# HV1.net
KiCad netlist of a schematic drawn in Altium Designer
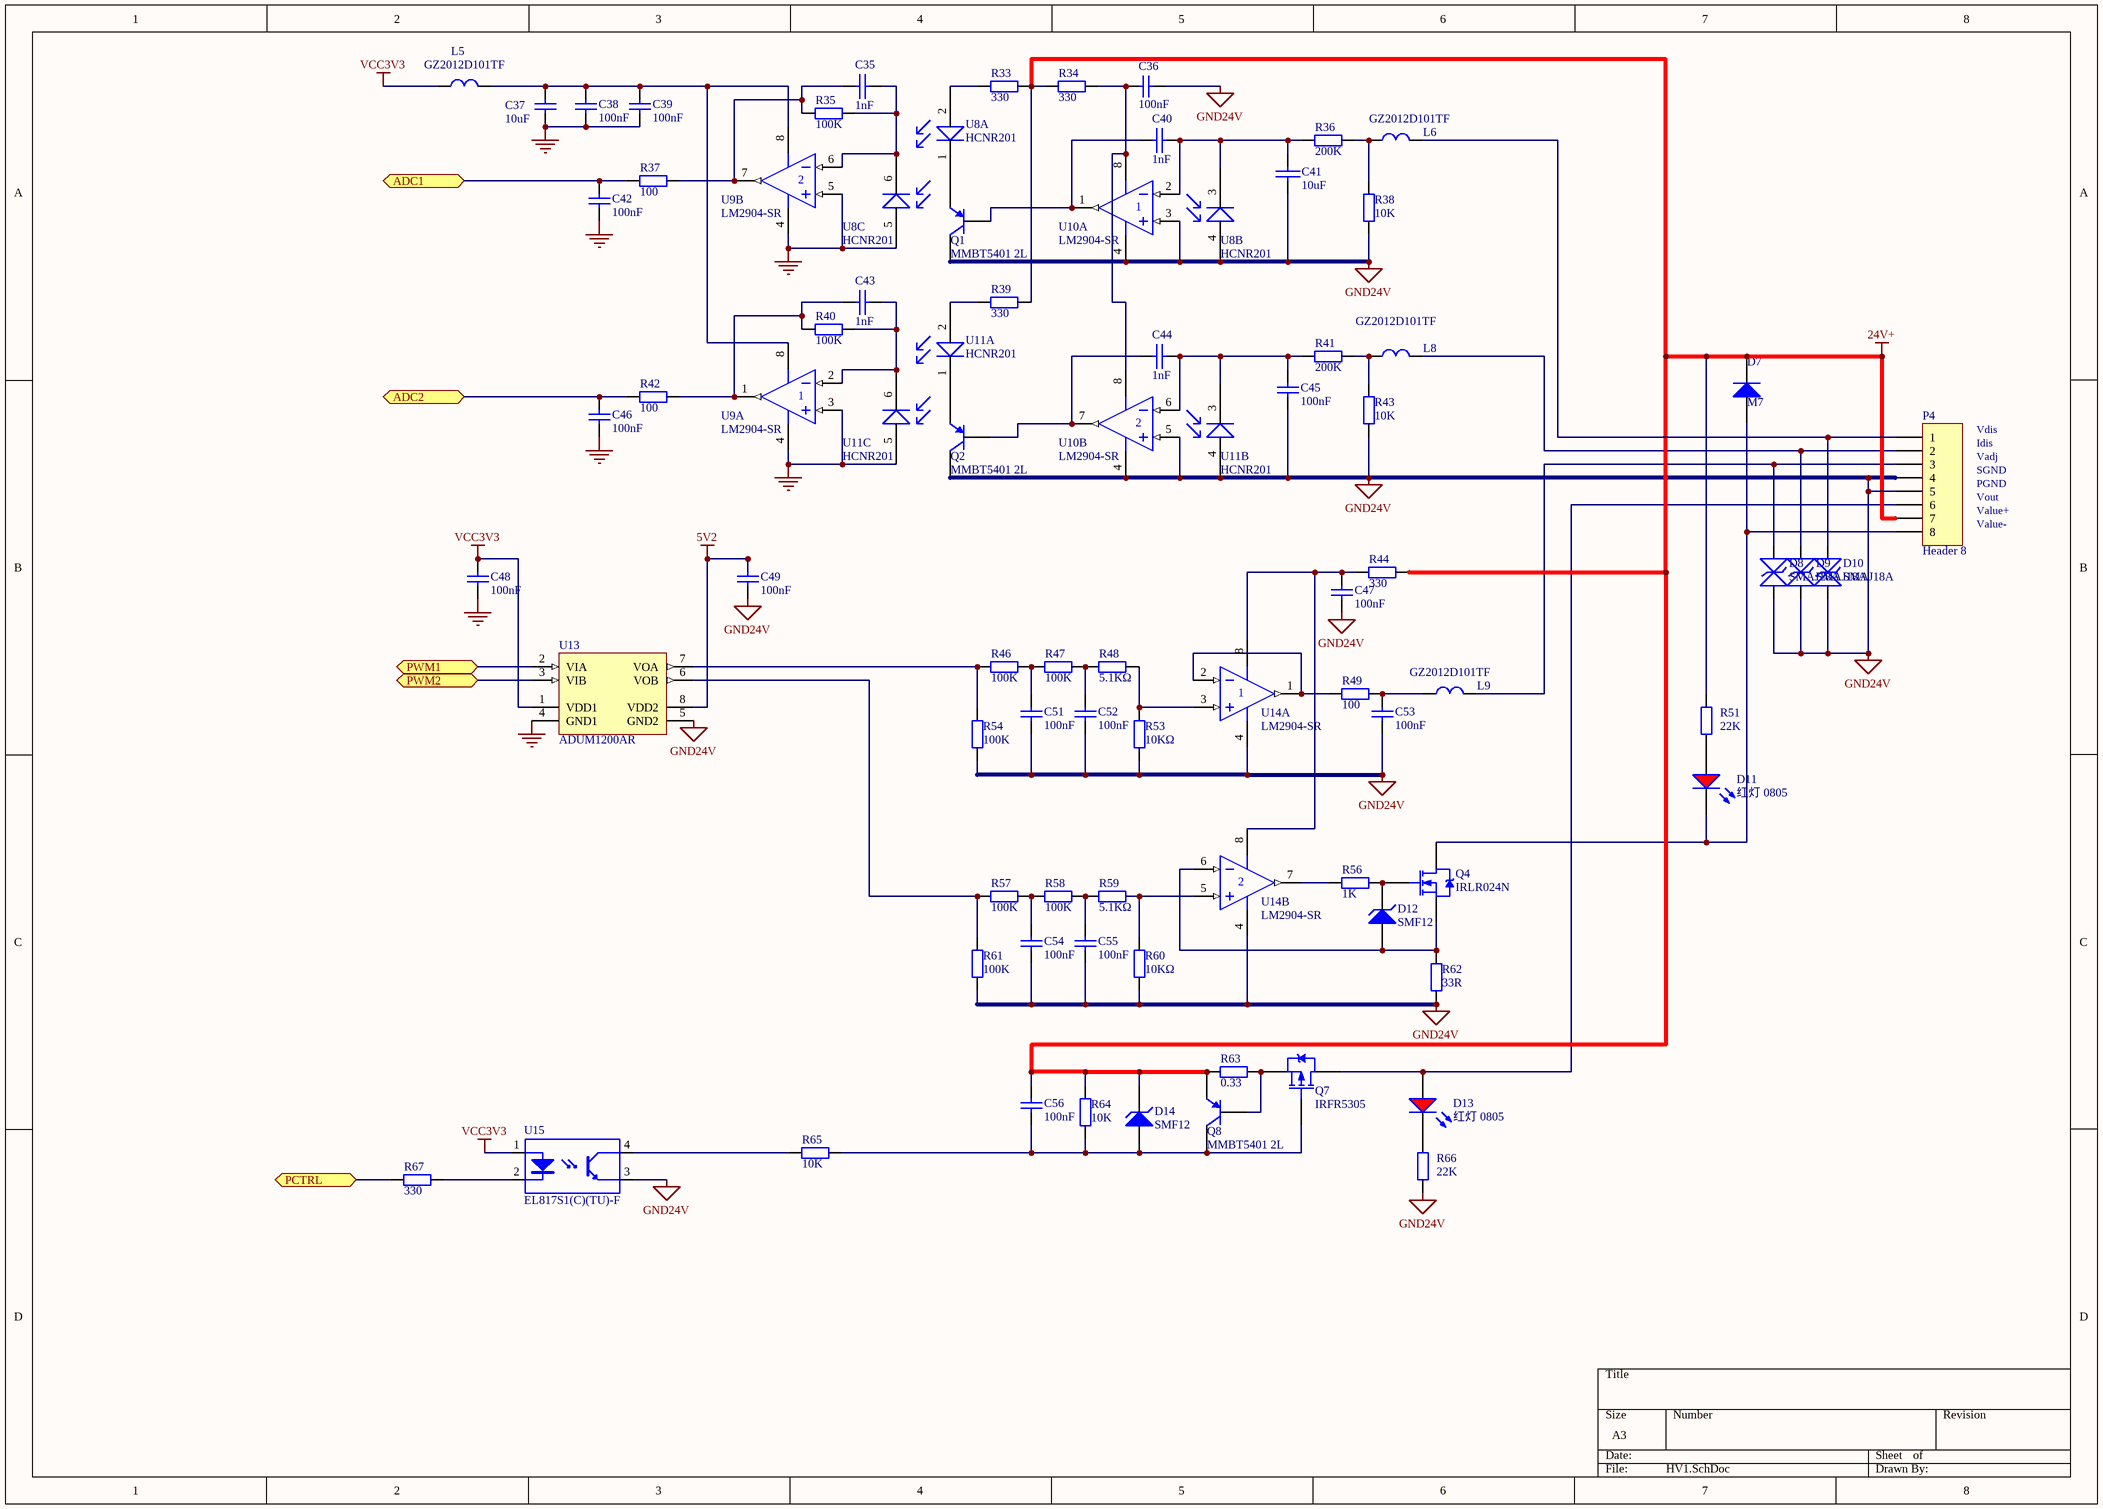
[diagram p0: HV1.SchDoc]

(export (version "E")
  (design (tool "Eeschema 10.0.6"))
  (components
    (comp (ref "C35")
      (value "1nF")
      (footprint "0805_C")
      (description "Capacitor")
      (libsource (lib "*") (part "CAP"))
    )
    (comp (ref "C36")
      (value "100nF")
      (footprint "0805_C")
      (description "贴片电容")
      (libsource (lib "Miscellaneous Devices LC") (part "0805 100nF(104) 10% 50V"))
    )
    (comp (ref "C37")
      (value "10uF")
      (footprint "0805_C")
      (description "贴片电容")
      (libsource (lib "Miscellaneous Devices LC") (part "1206 10uF (106) 10% 50V"))
    )
    (comp (ref "C38")
      (value "100nF")
      (footprint "0805_C")
      (description "贴片电容")
      (libsource (lib "Miscellaneous Devices LC") (part "0805 100nF(104) 10% 50V"))
    )
    (comp (ref "C39")
      (value "100nF")
      (footprint "0805_C")
      (description "贴片电容")
      (libsource (lib "Miscellaneous Devices LC") (part "0805 100nF(104) 10% 50V"))
    )
    (comp (ref "C40")
      (value "1nF")
      (footprint "0805_C")
      (description "Capacitor")
      (libsource (lib "*") (part "CAP"))
    )
    (comp (ref "C41")
      (value "10uF")
      (footprint "0805_C")
      (description "Capacitor")
      (libsource (lib "*") (part "CC"))
    )
    (comp (ref "C42")
      (value "100nF")
      (footprint "0805_C")
      (description "贴片电容")
      (libsource (lib "Miscellaneous Devices LC") (part "0805 100nF(104) 10% 50V"))
    )
    (comp (ref "C43")
      (value "1nF")
      (footprint "0805_C")
      (description "Capacitor")
      (libsource (lib "*") (part "CAP"))
    )
    (comp (ref "C44")
      (value "1nF")
      (footprint "0805_C")
      (description "Capacitor")
      (libsource (lib "*") (part "CAP"))
    )
    (comp (ref "C45")
      (value "100nF")
      (footprint "0805_C")
      (description "贴片电容")
      (libsource (lib "Miscellaneous Devices LC") (part "0805 100nF(104) 10% 50V"))
    )
    (comp (ref "C46")
      (value "100nF")
      (footprint "0805_C")
      (description "贴片电容")
      (libsource (lib "Miscellaneous Devices LC") (part "0805 100nF(104) 10% 50V"))
    )
    (comp (ref "C47")
      (value "100nF")
      (footprint "0805_C")
      (description "贴片电容")
      (libsource (lib "Miscellaneous Devices LC") (part "0805 100nF(104) 10% 50V"))
    )
    (comp (ref "C48")
      (value "100nF")
      (footprint "0805_C")
      (description "贴片电容")
      (libsource (lib "Miscellaneous Devices LC") (part "0805 100nF(104) 10% 50V"))
    )
    (comp (ref "C49")
      (value "100nF")
      (footprint "0805_C")
      (description "贴片电容")
      (libsource (lib "Miscellaneous Devices LC") (part "0805 100nF(104) 10% 50V"))
    )
    (comp (ref "C51")
      (value "100nF")
      (footprint "0805_C")
      (description "贴片电容")
      (libsource (lib "Miscellaneous Devices LC") (part "0805 100nF(104) 10% 50V"))
    )
    (comp (ref "C52")
      (value "100nF")
      (footprint "0805_C")
      (description "贴片电容")
      (libsource (lib "Miscellaneous Devices LC") (part "0805 100nF(104) 10% 50V"))
    )
    (comp (ref "C53")
      (value "100nF")
      (footprint "0805_C")
      (description "贴片电容")
      (libsource (lib "Miscellaneous Devices LC") (part "0805 100nF(104) 10% 50V"))
    )
    (comp (ref "C54")
      (value "100nF")
      (footprint "0805_C")
      (description "贴片电容")
      (libsource (lib "Miscellaneous Devices LC") (part "0805 100nF(104) 10% 50V"))
    )
    (comp (ref "C55")
      (value "100nF")
      (footprint "0805_C")
      (description "贴片电容")
      (libsource (lib "Miscellaneous Devices LC") (part "0805 100nF(104) 10% 50V"))
    )
    (comp (ref "C56")
      (value "100nF")
      (footprint "0805_C")
      (description "贴片电容")
      (libsource (lib "Miscellaneous Devices LC") (part "0805 100nF(104) 10% 50V"))
    )
    (comp (ref "D7")
      (value "M7")
      (footprint "SMA(DO-214AC)_S1")
      (description "二极管")
      (libsource (lib "Miscellaneous Devices LC") (part "SMA(DO-214AC) M7"))
    )
    (comp (ref "D8") (value "SMAJ18A") (footprint "SMA") (libsource (lib "IC") (part "TVS")))
    (comp (ref "D9") (value "SMAJ18A") (footprint "SMA") (libsource (lib "IC") (part "TVS")))
    (comp (ref "D10") (value "SMAJ18A") (footprint "SMA") (libsource (lib "IC") (part "TVS")))
    (comp (ref "D11")
      (value "红灯 0805")
      (footprint "0805_LED_S1")
      (description "发光二极管")
      (libsource (lib "Miscellaneous Devices LC") (part "0805 红灯"))
    )
    (comp (ref "D12")
      (value "SMF12")
      (footprint "Miscellaneous Devices LC:SOD-123")
      (description "Zener Diode")
      (fields (field (name "PUBLISHER") "Altium Limited"))
      (libsource (lib "Miscellaneous Devices") (part "D Zener"))
    )
    (comp (ref "D13")
      (value "红灯 0805")
      (footprint "0805_LED_S1")
      (description "发光二极管")
      (libsource (lib "Miscellaneous Devices LC") (part "0805 红灯"))
    )
    (comp (ref "D14")
      (value "SMF12")
      (footprint "Miscellaneous Devices LC:SOD-123")
      (description "Zener Diode")
      (fields (field (name "PUBLISHER") "Altium Limited"))
      (libsource (lib "Miscellaneous Devices") (part "D Zener"))
    )
    (comp (ref "L5") (value "GZ2012D101TF") (footprint "0805_L") (libsource (lib "Devices") (part "L1")))
    (comp (ref "L6") (value "GZ2012D101TF") (footprint "0805_L") (libsource (lib "Devices") (part "L1")))
    (comp (ref "L8") (value "GZ2012D101TF") (footprint "0805_L") (libsource (lib "Devices") (part "L1")))
    (comp (ref "L9") (value "GZ2012D101TF") (footprint "0805_L") (libsource (lib "") (part "L1_1")))
    (comp (ref "P4")
      (value "Header 8")
      (footprint "MC1.5/8-ST-3.81")
      (description "Header, 8-Pin")
      (fields (field (name "PUBLISHER") "Altium Limited"))
      (libsource (lib "Miscellaneous Connectors") (part "Header 8"))
    )
    (comp (ref "Q1")
      (value "MMBT5401 2L")
      (footprint "SOT-23(SOT-23-3)")
      (description "三极管")
      (libsource (lib "Miscellaneous Devices LC") (part "SOT-23 MMBT5401 2L"))
    )
    (comp (ref "Q2")
      (value "MMBT5401 2L")
      (footprint "SOT-23(SOT-23-3)")
      (description "三极管")
      (libsource (lib "Miscellaneous Devices LC") (part "SOT-23 MMBT5401 2L"))
    )
    (comp (ref "Q4")
      (value "IRLR024N")
      (footprint "TO-252AA_N")
      (description "HEXFET Power MOSFET")
      (fields (field (name "PUBLISHER") "Altium Limited"))
      (libsource (lib "IR Discrete MOSFET - Power") (part "IRLR024N"))
    )
    (comp (ref "Q7")
      (value "IRFR5305")
      (footprint "TO-252AA_N")
      (description "HEXFET Power MOSFET")
      (fields (field (name "PUBLISHER") "Altium Limited"))
      (libsource (lib "IR Discrete MOSFET - Power") (part "IRFR5305"))
    )
    (comp (ref "Q8")
      (value "MMBT5401 2L")
      (footprint "SOT-23(SOT-23-3)")
      (description "三极管")
      (libsource (lib "Miscellaneous Devices LC") (part "SOT-23 MMBT5401 2L"))
    )
    (comp (ref "R33")
      (value "330")
      (footprint "0805_R")
      (description "Resistor")
      (fields (field (name "PUBLISHER") "Altium Limited"))
      (libsource (lib "") (part "Res2_2"))
    )
    (comp (ref "R34")
      (value "330")
      (footprint "0805_R")
      (description "Resistor")
      (fields (field (name "PUBLISHER") "Altium Limited"))
      (libsource (lib "") (part "Res2_2"))
    )
    (comp (ref "R35")
      (value "100K")
      (footprint "0805_R")
      (description "Resistor")
      (fields (field (name "PUBLISHER") "Altium Limited"))
      (libsource (lib "Miscellaneous Devices") (part "Res2"))
    )
    (comp (ref "R36")
      (value "200K")
      (footprint "0805_R")
      (description "Resistor")
      (fields (field (name "PUBLISHER") "Altium Limited"))
      (libsource (lib "Miscellaneous Devices") (part "Res2"))
    )
    (comp (ref "R37")
      (value "100")
      (footprint "0805_R")
      (description "Resistor")
      (fields (field (name "PUBLISHER") "Altium Limited"))
      (libsource (lib "") (part "Res2_2"))
    )
    (comp (ref "R38")
      (value "10K")
      (footprint "0805_R")
      (description "Resistor")
      (fields (field (name "PUBLISHER") "Altium Limited"))
      (libsource (lib "") (part "Res2_4"))
    )
    (comp (ref "R39")
      (value "330")
      (footprint "0805_R")
      (description "Resistor")
      (fields (field (name "PUBLISHER") "Altium Limited"))
      (libsource (lib "") (part "Res2_2"))
    )
    (comp (ref "R40")
      (value "100K")
      (footprint "0805_R")
      (description "Resistor")
      (fields (field (name "PUBLISHER") "Altium Limited"))
      (libsource (lib "Miscellaneous Devices") (part "Res2"))
    )
    (comp (ref "R41")
      (value "200K")
      (footprint "0805_R")
      (description "Resistor")
      (fields (field (name "PUBLISHER") "Altium Limited"))
      (libsource (lib "Miscellaneous Devices") (part "Res2"))
    )
    (comp (ref "R42")
      (value "100")
      (footprint "0805_R")
      (description "Resistor")
      (fields (field (name "PUBLISHER") "Altium Limited"))
      (libsource (lib "") (part "Res2_2"))
    )
    (comp (ref "R43")
      (value "10K")
      (footprint "0805_R")
      (description "Resistor")
      (fields (field (name "PUBLISHER") "Altium Limited"))
      (libsource (lib "") (part "Res2_4"))
    )
    (comp (ref "R44")
      (value "330")
      (footprint "0805_R")
      (description "贴片电阻")
      (libsource (lib "Miscellaneous Devices LC") (part "0805 100Ω (1000) 1%"))
    )
    (comp (ref "R46")
      (value "100K")
      (footprint "0805_R")
      (description "贴片电阻")
      (libsource (lib "") (part "0805 100KΩ (1003) 1%_1"))
    )
    (comp (ref "R47")
      (value "100K")
      (footprint "0805_R")
      (description "贴片电阻")
      (libsource (lib "") (part "0805 100KΩ (1003) 1%_1"))
    )
    (comp (ref "R48")
      (value "5.1KΩ")
      (footprint "0805_R")
      (description "贴片电阻")
      (libsource (lib "Miscellaneous Devices LC") (part "0805 5.1KΩ (5101) 1%"))
    )
    (comp (ref "R49")
      (value "100")
      (footprint "0805_R")
      (description "贴片电阻")
      (libsource (lib "") (part "0805 100KΩ (1003) 1%_1"))
    )
    (comp (ref "R51")
      (value "22K")
      (footprint "R0805")
      (description "贴片电阻")
      (libsource (lib "电阻") (part "RMK2012KBxxx（10～1M）F"))
    )
    (comp (ref "R53")
      (value "10KΩ")
      (footprint "0805_R")
      (description "贴片电阻")
      (libsource (lib "Miscellaneous Devices LC") (part "0805 10KΩ (1002) 1%"))
    )
    (comp (ref "R54")
      (value "100K")
      (footprint "0805_R")
      (description "贴片电阻")
      (libsource (lib "Miscellaneous Devices LC") (part "0805 100KΩ (1003) 1%"))
    )
    (comp (ref "R56")
      (value "1K")
      (footprint "0805_R")
      (description "贴片电阻")
      (libsource (lib "") (part "0805 100KΩ (1003) 1%_1"))
    )
    (comp (ref "R57")
      (value "100K")
      (footprint "0805_R")
      (description "贴片电阻")
      (libsource (lib "") (part "0805 100KΩ (1003) 1%_1"))
    )
    (comp (ref "R58")
      (value "100K")
      (footprint "0805_R")
      (description "贴片电阻")
      (libsource (lib "") (part "0805 100KΩ (1003) 1%_1"))
    )
    (comp (ref "R59")
      (value "5.1KΩ")
      (footprint "0805_R")
      (description "贴片电阻")
      (libsource (lib "Miscellaneous Devices LC") (part "0805 5.1KΩ (5101) 1%"))
    )
    (comp (ref "R60")
      (value "10KΩ")
      (footprint "0805_R")
      (description "贴片电阻")
      (libsource (lib "Miscellaneous Devices LC") (part "0805 10KΩ (1002) 1%"))
    )
    (comp (ref "R61")
      (value "100K")
      (footprint "0805_R")
      (description "贴片电阻")
      (libsource (lib "Miscellaneous Devices LC") (part "0805 100KΩ (1003) 1%"))
    )
    (comp (ref "R62")
      (value "33R")
      (footprint "R2512")
      (description "Resistor")
      (fields (field (name "PUBLISHER") "Altium Limited"))
      (libsource (lib "") (part "Res2_5"))
    )
    (comp (ref "R63")
      (value "0.33")
      (footprint "R2512")
      (description "Resistor")
      (fields (field (name "PUBLISHER") "Altium Limited"))
      (libsource (lib "") (part "Res2_1"))
    )
    (comp (ref "R64")
      (value "10K")
      (footprint "0805_R")
      (description "Resistor")
      (fields (field (name "PUBLISHER") "Altium Limited"))
      (libsource (lib "") (part "Res2_5"))
    )
    (comp (ref "R65")
      (value "10K")
      (footprint "0805_R")
      (description "Resistor")
      (fields (field (name "PUBLISHER") "Altium Limited"))
      (libsource (lib "") (part "Res2_1"))
    )
    (comp (ref "R66")
      (value "22K")
      (footprint "0805_R")
      (description "贴片电阻")
      (libsource (lib "电阻") (part "RMK2012KBxxx（10～1M）F"))
    )
    (comp (ref "R67")
      (value "330")
      (footprint "0805_R")
      (description "Resistor")
      (fields (field (name "PUBLISHER") "Altium Limited"))
      (libsource (lib "") (part "Res2_3"))
    )
    (comp (ref "U8") (value "HCNR201") (footprint "SMD-8_9.0mm") (libsource (lib "*") (part "HCNR201")))
    (comp (ref "U9")
      (value "LM2904-SR")
      (footprint "SOIC-8_150mil")
      (description "Dual Low-Power Operational Amplifier")
      (fields (field (name "PUBLISHER") "Altium Limited"))
      (libsource (lib "Miscellaneous Devices LC") (part "LM2904D"))
    )
    (comp (ref "U10")
      (value "LM2904-SR")
      (footprint "SOIC-8_150mil")
      (description "Dual Low-Power Operational Amplifier")
      (fields (field (name "PUBLISHER") "Altium Limited"))
      (libsource (lib "Miscellaneous Devices LC") (part "LM2904D"))
    )
    (comp (ref "U11") (value "HCNR201") (footprint "SMD-8_9.0mm") (libsource (lib "*") (part "HCNR201")))
    (comp (ref "U13")
      (value "ADUM1200AR")
      (footprint "ADI-R-8_N")
      (fields (field (name "MANUFACTURER") "Analog Devices"))
      (libsource (lib "Analog Devices Interface and Isolation Digital Isolators") (part "ADUM1200AR"))
    )
    (comp (ref "U14")
      (value "LM2904-SR")
      (footprint "SOIC-8_150mil")
      (description "Dual Low-Power Operational Amplifier")
      (fields (field (name "PUBLISHER") "Altium Limited"))
      (libsource (lib "Miscellaneous Devices LC") (part "LM2904D"))
    )
    (comp (ref "U15")
      (value "EL817S1(C)(TU)-F")
      (footprint "LC-SMD-4")
      (libsource (lib "IC") (part "TLP521"))
    )
  )
  (nets
    (net (code "1") (name "/ADC1") (class "Default")
      (node (ref "C42") (pin "2") (pinfunction "2_2") (pintype "passive"))
      (node (ref "R37") (pin "2") (pinfunction "2_2") (pintype "passive"))
    )
    (net (code "2") (name "/ADC2") (class "Default")
      (node (ref "C46") (pin "2") (pinfunction "2_2") (pintype "passive"))
      (node (ref "R42") (pin "2") (pinfunction "2_2") (pintype "passive"))
    )
    (net (code "3") (name "/PCTRL") (class "Default")
      (node (ref "R67") (pin "1") (pinfunction "1_1") (pintype "passive"))
    )
    (net (code "4") (name "/PWM1") (class "Default")
      (node (ref "U13") (pin "2") (pinfunction "VIA_2") (pintype "input"))
    )
    (net (code "5") (name "/PWM2") (class "Default")
      (node (ref "U13") (pin "3") (pinfunction "VIB_3") (pintype "input"))
    )
    (net (code "6") (name "5V2") (class "Default")
      (node (ref "C49") (pin "2") (pinfunction "2_2") (pintype "passive"))
      (node (ref "U13") (pin "8") (pinfunction "VDD2_8") (pintype "power_in"))
    )
    (net (code "7") (name "24V+") (class "Default")
      (node (ref "C56") (pin "2") (pinfunction "2_2") (pintype "passive"))
      (node (ref "D14") (pin "2") (pinfunction "K_2") (pintype "passive"))
      (node (ref "D7") (pin "2") (pinfunction "K_2") (pintype "passive"))
      (node (ref "P4") (pin "7") (pinfunction "7_7") (pintype "passive"))
      (node (ref "Q8") (pin "2") (pinfunction "E_2") (pintype "passive"))
      (node (ref "R33") (pin "1") (pinfunction "1_1") (pintype "passive"))
      (node (ref "R34") (pin "2") (pinfunction "2_2") (pintype "passive"))
      (node (ref "R39") (pin "1") (pinfunction "1_1") (pintype "passive"))
      (node (ref "R44") (pin "1") (pinfunction "1_1") (pintype "passive"))
      (node (ref "R51") (pin "1") (pinfunction "1_1") (pintype "passive"))
      (node (ref "R63") (pin "2") (pinfunction "2_2") (pintype "passive"))
      (node (ref "R64") (pin "2") (pinfunction "2_2") (pintype "passive"))
    )
    (net (code "8") (name "GND") (class "Default")
      (node (ref "C37") (pin "1") (pinfunction "1_1") (pintype "passive"))
      (node (ref "C38") (pin "1") (pinfunction "1_1") (pintype "passive"))
      (node (ref "C39") (pin "1") (pinfunction "1_1") (pintype "passive"))
      (node (ref "C42") (pin "1") (pinfunction "1_1") (pintype "passive"))
      (node (ref "C46") (pin "1") (pinfunction "1_1") (pintype "passive"))
      (node (ref "C48") (pin "1") (pinfunction "1_1") (pintype "passive"))
      (node (ref "U11") (pin "5") (pinfunction "+_5") (pintype "passive"))
      (node (ref "U13") (pin "4") (pinfunction "GND1_4") (pintype "power_in"))
      (node (ref "U8") (pin "5") (pinfunction "+_5") (pintype "passive"))
      (node (ref "U9") (pin "3") (pinfunction "IN+_3") (pintype "input"))
      (node (ref "U9") (pin "4") (pinfunction "V-_4") (pintype "power_in"))
      (node (ref "U9") (pin "5") (pinfunction "IN+_5") (pintype "input"))
    )
    (net (code "9") (name "GND24V") (class "Default")
      (node (ref "C36") (pin "1") (pinfunction "1_1") (pintype "passive"))
      (node (ref "C41") (pin "1") (pinfunction "1_1") (pintype "passive"))
      (node (ref "C45") (pin "1") (pinfunction "1_1") (pintype "passive"))
      (node (ref "C47") (pin "1") (pinfunction "1_1") (pintype "passive"))
      (node (ref "C49") (pin "1") (pinfunction "1_1") (pintype "passive"))
      (node (ref "C51") (pin "1") (pinfunction "1_1") (pintype "passive"))
      (node (ref "C52") (pin "1") (pinfunction "1_1") (pintype "passive"))
      (node (ref "C53") (pin "1") (pinfunction "1_1") (pintype "passive"))
      (node (ref "C54") (pin "1") (pinfunction "1_1") (pintype "passive"))
      (node (ref "C55") (pin "1") (pinfunction "1_1") (pintype "passive"))
      (node (ref "D10") (pin "1") (pinfunction "1_1") (pintype "passive"))
      (node (ref "D8") (pin "1") (pinfunction "1_1") (pintype "passive"))
      (node (ref "D9") (pin "1") (pinfunction "1_1") (pintype "passive"))
      (node (ref "P4") (pin "4") (pinfunction "4_4") (pintype "passive"))
      (node (ref "P4") (pin "5") (pinfunction "5_5") (pintype "passive"))
      (node (ref "Q1") (pin "3") (pinfunction "C_3") (pintype "passive"))
      (node (ref "Q2") (pin "3") (pinfunction "C_3") (pintype "passive"))
      (node (ref "R38") (pin "1") (pinfunction "1_1") (pintype "passive"))
      (node (ref "R43") (pin "1") (pinfunction "1_1") (pintype "passive"))
      (node (ref "R53") (pin "2") (pinfunction "2_2") (pintype "passive"))
      (node (ref "R54") (pin "2") (pinfunction "2_2") (pintype "passive"))
      (node (ref "R60") (pin "2") (pinfunction "2_2") (pintype "passive"))
      (node (ref "R61") (pin "2") (pinfunction "2_2") (pintype "passive"))
      (node (ref "R62") (pin "1") (pinfunction "1_1") (pintype "passive"))
      (node (ref "R66") (pin "2") (pinfunction "2_2") (pintype "passive"))
      (node (ref "U10") (pin "3") (pinfunction "IN+_3") (pintype "input"))
      (node (ref "U10") (pin "4") (pinfunction "V-_4") (pintype "power_in"))
      (node (ref "U10") (pin "5") (pinfunction "IN+_5") (pintype "input"))
      (node (ref "U11") (pin "4") (pinfunction "+_4") (pintype "passive"))
      (node (ref "U13") (pin "5") (pinfunction "GND2_5") (pintype "power_in"))
      (node (ref "U14") (pin "4") (pinfunction "V-_4") (pintype "power_in"))
      (node (ref "U15") (pin "3") (pinfunction "E_3") (pintype "passive"))
      (node (ref "U8") (pin "4") (pinfunction "+_4") (pintype "passive"))
    )
    (net (code "10") (name "Net-(C51-Pad2)") (class "Default")
      (node (ref "C51") (pin "2") (pinfunction "2_2") (pintype "passive"))
      (node (ref "R46") (pin "1") (pinfunction "1_1") (pintype "passive"))
      (node (ref "R47") (pin "2") (pinfunction "2_2") (pintype "passive"))
    )
    (net (code "11") (name "Net-(C52-Pad2)") (class "Default")
      (node (ref "C52") (pin "2") (pinfunction "2_2") (pintype "passive"))
      (node (ref "R47") (pin "1") (pinfunction "1_1") (pintype "passive"))
      (node (ref "R48") (pin "2") (pinfunction "2_2") (pintype "passive"))
    )
    (net (code "12") (name "Net-(C53-Pad2)") (class "Default")
      (node (ref "C53") (pin "2") (pinfunction "2_2") (pintype "passive"))
      (node (ref "L9") (pin "2") (pinfunction "2_2") (pintype "passive"))
      (node (ref "R49") (pin "1") (pinfunction "1_1") (pintype "passive"))
    )
    (net (code "13") (name "Net-(C54-Pad2)") (class "Default")
      (node (ref "C54") (pin "2") (pinfunction "2_2") (pintype "passive"))
      (node (ref "R57") (pin "1") (pinfunction "1_1") (pintype "passive"))
      (node (ref "R58") (pin "2") (pinfunction "2_2") (pintype "passive"))
    )
    (net (code "14") (name "Net-(C55-Pad2)") (class "Default")
      (node (ref "C55") (pin "2") (pinfunction "2_2") (pintype "passive"))
      (node (ref "R58") (pin "1") (pinfunction "1_1") (pintype "passive"))
      (node (ref "R59") (pin "2") (pinfunction "2_2") (pintype "passive"))
    )
    (net (code "15") (name "Net-(D7-A)") (class "Default")
      (node (ref "D11") (pin "K") (pinfunction "K_K") (pintype "passive"))
      (node (ref "D7") (pin "1") (pinfunction "A_1") (pintype "passive"))
      (node (ref "P4") (pin "8") (pinfunction "8_8") (pintype "passive"))
      (node (ref "Q4") (pin "4") (pinfunction "D_4") (pintype "passive"))
    )
    (net (code "16") (name "Net-(D8-Pad2)") (class "Default")
      (node (ref "D8") (pin "2") (pinfunction "2_2") (pintype "passive"))
      (node (ref "L9") (pin "1") (pinfunction "1_1") (pintype "passive"))
      (node (ref "P4") (pin "3") (pinfunction "3_3") (pintype "passive"))
    )
    (net (code "17") (name "Net-(D9-Pad2)") (class "Default")
      (node (ref "D9") (pin "2") (pinfunction "2_2") (pintype "passive"))
      (node (ref "L8") (pin "2") (pinfunction "2_2") (pintype "passive"))
      (node (ref "P4") (pin "2") (pinfunction "2_2") (pintype "passive"))
    )
    (net (code "18") (name "Net-(D10-Pad2)") (class "Default")
      (node (ref "D10") (pin "2") (pinfunction "2_2") (pintype "passive"))
      (node (ref "L6") (pin "2") (pinfunction "2_2") (pintype "passive"))
      (node (ref "P4") (pin "1") (pinfunction "1_1") (pintype "passive"))
    )
    (net (code "19") (name "Net-(D11-PadA)") (class "Default")
      (node (ref "D11") (pin "A") (pinfunction "A_A") (pintype "passive"))
      (node (ref "R51") (pin "2") (pinfunction "2_2") (pintype "passive"))
    )
    (net (code "20") (name "Net-(D12-A)") (class "Default")
      (node (ref "D12") (pin "1") (pinfunction "A_1") (pintype "passive"))
      (node (ref "Q4") (pin "3") (pinfunction "S_3") (pintype "passive"))
      (node (ref "R62") (pin "2") (pinfunction "2_2") (pintype "passive"))
      (node (ref "U14") (pin "6") (pinfunction "IN-_6") (pintype "input"))
    )
    (net (code "21") (name "Net-(D12-K)") (class "Default")
      (node (ref "D12") (pin "2") (pinfunction "K_2") (pintype "passive"))
      (node (ref "Q4") (pin "1") (pinfunction "G_1") (pintype "passive"))
      (node (ref "R56") (pin "1") (pinfunction "1_1") (pintype "passive"))
    )
    (net (code "22") (name "Net-(D13-PadK)") (class "Default")
      (node (ref "D13") (pin "K") (pinfunction "K_K") (pintype "passive"))
      (node (ref "R66") (pin "1") (pinfunction "1_1") (pintype "passive"))
    )
    (net (code "23") (name "Net-(D14-A)") (class "Default")
      (node (ref "C56") (pin "1") (pinfunction "1_1") (pintype "passive"))
      (node (ref "D14") (pin "1") (pinfunction "A_1") (pintype "passive"))
      (node (ref "Q7") (pin "1") (pinfunction "G_1") (pintype "passive"))
      (node (ref "Q8") (pin "3") (pinfunction "C_3") (pintype "passive"))
      (node (ref "R64") (pin "1") (pinfunction "1_1") (pintype "passive"))
      (node (ref "R65") (pin "1") (pinfunction "1_1") (pintype "passive"))
    )
    (net (code "24") (name "Net-(L6-Pad1)") (class "Default")
      (node (ref "L6") (pin "1") (pinfunction "1_1") (pintype "passive"))
      (node (ref "R36") (pin "2") (pinfunction "2_2") (pintype "passive"))
      (node (ref "R38") (pin "2") (pinfunction "2_2") (pintype "passive"))
    )
    (net (code "25") (name "Net-(L8-Pad1)") (class "Default")
      (node (ref "L8") (pin "1") (pinfunction "1_1") (pintype "passive"))
      (node (ref "R41") (pin "2") (pinfunction "2_2") (pintype "passive"))
      (node (ref "R43") (pin "2") (pinfunction "2_2") (pintype "passive"))
    )
    (net (code "26") (name "Net-(Q1-B)") (class "Default")
      (node (ref "C40") (pin "2") (pinfunction "2_2") (pintype "passive"))
      (node (ref "Q1") (pin "1") (pinfunction "B_1") (pintype "passive"))
      (node (ref "U10") (pin "1") (pinfunction "OUT_1") (pintype "output"))
    )
    (net (code "27") (name "Net-(Q1-E)") (class "Default")
      (node (ref "Q1") (pin "2") (pinfunction "E_2") (pintype "passive"))
      (node (ref "U8") (pin "1") (pinfunction "-_1") (pintype "passive"))
    )
    (net (code "28") (name "Net-(Q2-B)") (class "Default")
      (node (ref "C44") (pin "2") (pinfunction "2_2") (pintype "passive"))
      (node (ref "Q2") (pin "1") (pinfunction "B_1") (pintype "passive"))
      (node (ref "U10") (pin "7") (pinfunction "OUT_7") (pintype "output"))
    )
    (net (code "29") (name "Net-(Q2-E)") (class "Default")
      (node (ref "Q2") (pin "2") (pinfunction "E_2") (pintype "passive"))
      (node (ref "U11") (pin "1") (pinfunction "-_1") (pintype "passive"))
    )
    (net (code "30") (name "Net-(Q7-D)") (class "Default")
      (node (ref "D13") (pin "A") (pinfunction "A_A") (pintype "passive"))
      (node (ref "P4") (pin "6") (pinfunction "6_6") (pintype "passive"))
      (node (ref "Q7") (pin "4") (pinfunction "D_4") (pintype "passive"))
    )
    (net (code "31") (name "Net-(Q7-S)") (class "Default")
      (node (ref "Q7") (pin "3") (pinfunction "S_3") (pintype "passive"))
      (node (ref "Q8") (pin "1") (pinfunction "B_1") (pintype "passive"))
      (node (ref "R63") (pin "1") (pinfunction "1_1") (pintype "passive"))
    )
    (net (code "32") (name "Net-(U8A-+)") (class "Default")
      (node (ref "R33") (pin "2") (pinfunction "2_2") (pintype "passive"))
      (node (ref "U8") (pin "2") (pinfunction "+_2") (pintype "passive"))
    )
    (net (code "33") (name "Net-(U8C--)") (class "Default")
      (node (ref "C35") (pin "1") (pinfunction "1_1") (pintype "passive"))
      (node (ref "R35") (pin "2") (pinfunction "2_2") (pintype "passive"))
      (node (ref "U8") (pin "6") (pinfunction "-_6") (pintype "passive"))
      (node (ref "U9") (pin "6") (pinfunction "IN-_6") (pintype "input"))
    )
    (net (code "34") (name "Net-(U9A-OUT)") (class "Default")
      (node (ref "C43") (pin "2") (pinfunction "2_2") (pintype "passive"))
      (node (ref "R40") (pin "1") (pinfunction "1_1") (pintype "passive"))
      (node (ref "R42") (pin "1") (pinfunction "1_1") (pintype "passive"))
      (node (ref "U9") (pin "1") (pinfunction "OUT_1") (pintype "output"))
    )
    (net (code "35") (name "Net-(U9A-V+)") (class "Default")
      (node (ref "C37") (pin "2") (pinfunction "2_2") (pintype "passive"))
      (node (ref "C38") (pin "2") (pinfunction "2_2") (pintype "passive"))
      (node (ref "C39") (pin "2") (pinfunction "2_2") (pintype "passive"))
      (node (ref "L5") (pin "2") (pinfunction "2_2") (pintype "passive"))
      (node (ref "U9") (pin "8") (pinfunction "V+_8") (pintype "power_in"))
    )
    (net (code "36") (name "Net-(U9B-OUT)") (class "Default")
      (node (ref "C35") (pin "2") (pinfunction "2_2") (pintype "passive"))
      (node (ref "R35") (pin "1") (pinfunction "1_1") (pintype "passive"))
      (node (ref "R37") (pin "1") (pinfunction "1_1") (pintype "passive"))
      (node (ref "U9") (pin "7") (pinfunction "OUT_7") (pintype "output"))
    )
    (net (code "37") (name "Net-(U10A-IN-)") (class "Default")
      (node (ref "C40") (pin "1") (pinfunction "1_1") (pintype "passive"))
      (node (ref "C41") (pin "2") (pinfunction "2_2") (pintype "passive"))
      (node (ref "R36") (pin "1") (pinfunction "1_1") (pintype "passive"))
      (node (ref "U10") (pin "2") (pinfunction "IN-_2") (pintype "input"))
      (node (ref "U8") (pin "3") (pinfunction "-_3") (pintype "passive"))
    )
    (net (code "38") (name "Net-(U10A-V+)") (class "Default")
      (node (ref "C36") (pin "2") (pinfunction "2_2") (pintype "passive"))
      (node (ref "R34") (pin "1") (pinfunction "1_1") (pintype "passive"))
      (node (ref "U10") (pin "8") (pinfunction "V+_8") (pintype "power_in"))
    )
    (net (code "39") (name "Net-(U10B-IN-)") (class "Default")
      (node (ref "C44") (pin "1") (pinfunction "1_1") (pintype "passive"))
      (node (ref "C45") (pin "2") (pinfunction "2_2") (pintype "passive"))
      (node (ref "R41") (pin "1") (pinfunction "1_1") (pintype "passive"))
      (node (ref "U10") (pin "6") (pinfunction "IN-_6") (pintype "input"))
      (node (ref "U11") (pin "3") (pinfunction "-_3") (pintype "passive"))
    )
    (net (code "40") (name "Net-(U11A-+)") (class "Default")
      (node (ref "R39") (pin "2") (pinfunction "2_2") (pintype "passive"))
      (node (ref "U11") (pin "2") (pinfunction "+_2") (pintype "passive"))
    )
    (net (code "41") (name "Net-(U11C--)") (class "Default")
      (node (ref "C43") (pin "1") (pinfunction "1_1") (pintype "passive"))
      (node (ref "R40") (pin "2") (pinfunction "2_2") (pintype "passive"))
      (node (ref "U11") (pin "6") (pinfunction "-_6") (pintype "passive"))
      (node (ref "U9") (pin "2") (pinfunction "IN-_2") (pintype "input"))
    )
    (net (code "42") (name "Net-(U13-VOA)") (class "Default")
      (node (ref "R46") (pin "2") (pinfunction "2_2") (pintype "passive"))
      (node (ref "R54") (pin "1") (pinfunction "1_1") (pintype "passive"))
      (node (ref "U13") (pin "7") (pinfunction "VOA_7") (pintype "output"))
    )
    (net (code "43") (name "Net-(U13-VOB)") (class "Default")
      (node (ref "R57") (pin "2") (pinfunction "2_2") (pintype "passive"))
      (node (ref "R61") (pin "1") (pinfunction "1_1") (pintype "passive"))
      (node (ref "U13") (pin "6") (pinfunction "VOB_6") (pintype "output"))
    )
    (net (code "44") (name "Net-(U14A-IN+)") (class "Default")
      (node (ref "R48") (pin "1") (pinfunction "1_1") (pintype "passive"))
      (node (ref "R53") (pin "1") (pinfunction "1_1") (pintype "passive"))
      (node (ref "U14") (pin "3") (pinfunction "IN+_3") (pintype "input"))
    )
    (net (code "45") (name "Net-(U14A-IN-)") (class "Default")
      (node (ref "R49") (pin "2") (pinfunction "2_2") (pintype "passive"))
      (node (ref "U14") (pin "1") (pinfunction "OUT_1") (pintype "output"))
      (node (ref "U14") (pin "2") (pinfunction "IN-_2") (pintype "input"))
    )
    (net (code "46") (name "Net-(U14A-V+)") (class "Default")
      (node (ref "C47") (pin "2") (pinfunction "2_2") (pintype "passive"))
      (node (ref "R44") (pin "2") (pinfunction "2_2") (pintype "passive"))
      (node (ref "U14") (pin "8") (pinfunction "V+_8") (pintype "power_in"))
    )
    (net (code "47") (name "Net-(U14B-IN+)") (class "Default")
      (node (ref "R59") (pin "1") (pinfunction "1_1") (pintype "passive"))
      (node (ref "R60") (pin "1") (pinfunction "1_1") (pintype "passive"))
      (node (ref "U14") (pin "5") (pinfunction "IN+_5") (pintype "input"))
    )
    (net (code "48") (name "Net-(U14B-OUT)") (class "Default")
      (node (ref "R56") (pin "2") (pinfunction "2_2") (pintype "passive"))
      (node (ref "U14") (pin "7") (pinfunction "OUT_7") (pintype "output"))
    )
    (net (code "49") (name "Net-(U15-C)") (class "Default")
      (node (ref "R65") (pin "2") (pinfunction "2_2") (pintype "passive"))
      (node (ref "U15") (pin "4") (pinfunction "C_4") (pintype "passive"))
    )
    (net (code "50") (name "Net-(U15-K)") (class "Default")
      (node (ref "R67") (pin "2") (pinfunction "2_2") (pintype "passive"))
      (node (ref "U15") (pin "2") (pinfunction "K_2") (pintype "passive"))
    )
    (net (code "51") (name "VCC3V3") (class "Default")
      (node (ref "C48") (pin "2") (pinfunction "2_2") (pintype "passive"))
      (node (ref "L5") (pin "1") (pinfunction "1_1") (pintype "passive"))
      (node (ref "U13") (pin "1") (pinfunction "VDD1_1") (pintype "power_in"))
      (node (ref "U15") (pin "1") (pinfunction "A_1") (pintype "passive"))
    )
  )
)
